# Sheet1.net
KiCad netlist of a schematic drawn in Altium Designer
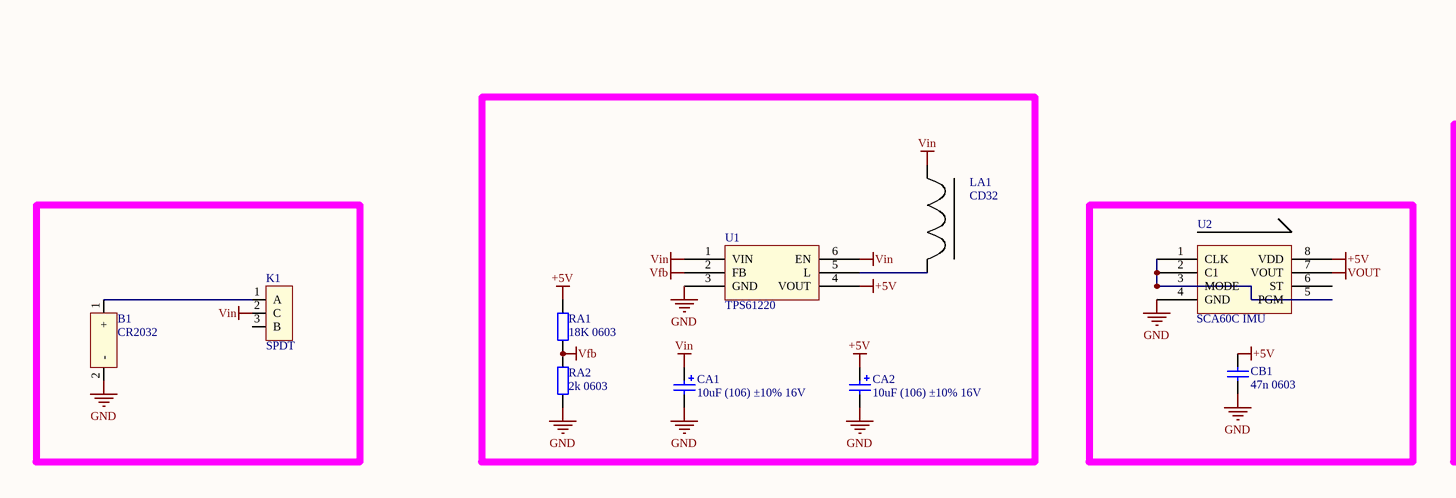
[diagram p0: Sheet1.SchDoc, left]
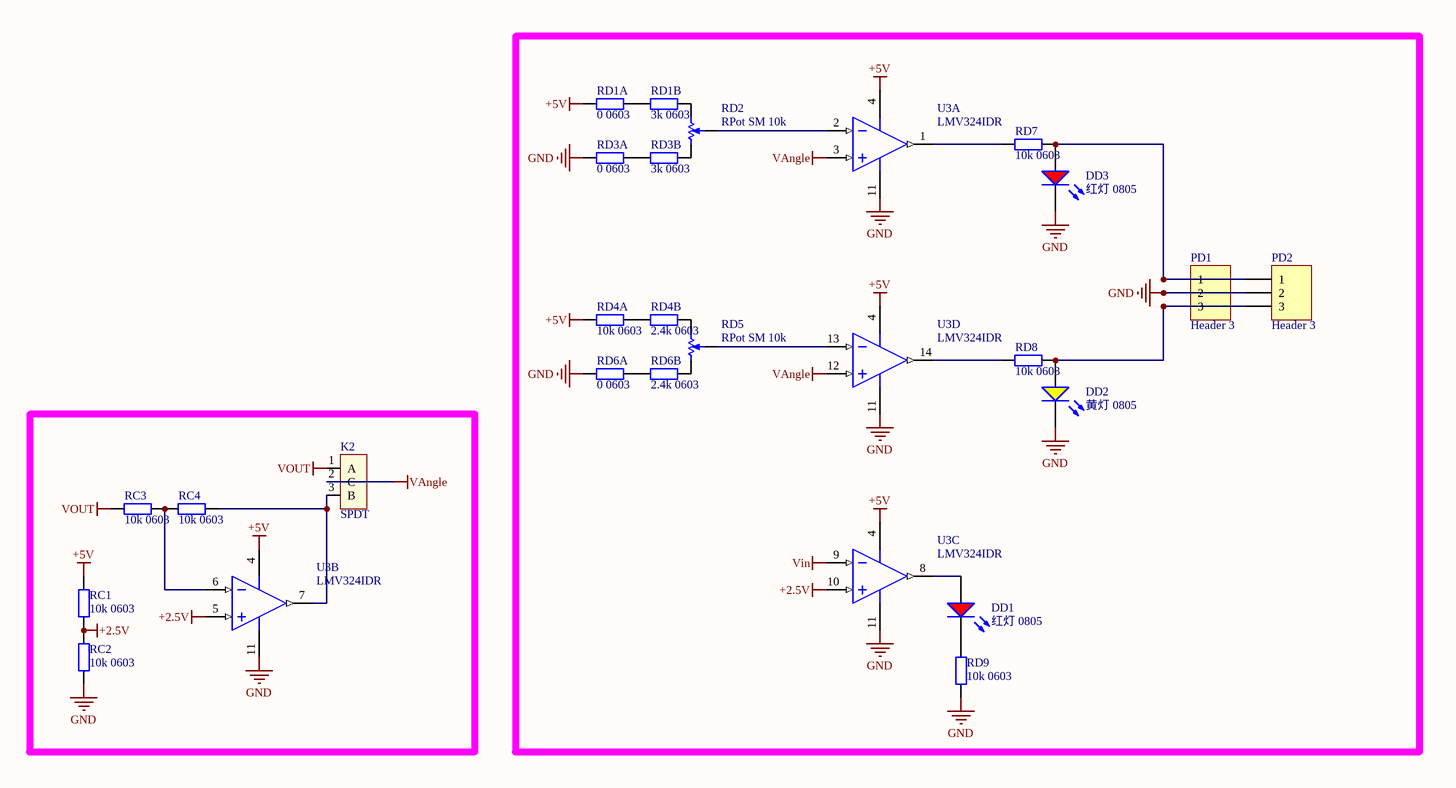
[diagram p1: Sheet1.SchDoc, right]

(export (version "E")
  (design (tool "Eeschema 10.0.6"))
  (components
    (comp (ref "B1")
      (value "CR2032")
      (footprint "CR2032")
      (description "Battery")
      (libsource (lib "EME_TX_Lib") (part "CR2032"))
    )
    (comp (ref "CA1")
      (value "10uF (106) ±10% 16V")
      (footprint "LC-CASE-A_3216")
      (description "钽电容")
      (libsource (lib "Miscellaneous Devices LC") (part "3216 10uF (106) 10% 16V"))
    )
    (comp (ref "CA2")
      (value "10uF (106) ±10% 16V")
      (footprint "LC-CASE-A_3216")
      (description "钽电容")
      (libsource (lib "Miscellaneous Devices LC") (part "3216 10uF (106) 10% 16V"))
    )
    (comp (ref "CB1")
      (value "47n 0603")
      (footprint "LC-0603_C")
      (description "贴片电容")
      (libsource (lib "Miscellaneous Devices LC") (part "0603 4.7nF (472) 10% 50V"))
    )
    (comp (ref "DD1")
      (value "红灯 0805")
      (footprint "LC-0805_LED_S1")
      (description "发光二极管")
      (libsource (lib "Miscellaneous Devices LC") (part "0805 红灯"))
    )
    (comp (ref "DD2")
      (value "黄灯 0805")
      (footprint "LC-0805_LED_S1")
      (description "发光二极管")
      (libsource (lib "Miscellaneous Devices LC") (part "0805 黄灯"))
    )
    (comp (ref "DD3")
      (value "红灯 0805")
      (footprint "LC-0805_LED_S1")
      (description "发光二极管")
      (libsource (lib "Miscellaneous Devices LC") (part "0805 红灯"))
    )
    (comp (ref "K1") (value "SPDT") (footprint "MSS22D18G2") (libsource (lib "EKAD") (part "MSS22D18G2")))
    (comp (ref "K2") (value "SPDT") (footprint "MSS22D18G2") (libsource (lib "EKAD") (part "MSS22D18G2")))
    (comp (ref "LA1") (value "CD32") (footprint "CD32") (libsource (lib "SMT_inductor") (part "CD32")))
    (comp (ref "PD1")
      (value "Header 3")
      (footprint "HDR1X3")
      (description "Header, 3-Pin")
      (fields (field (name "PUBLISHER") "Altium Limited"))
      (libsource (lib "Miscellaneous Connectors") (part "Header 3"))
    )
    (comp (ref "PD2")
      (value "Header 3")
      (footprint "HDR1X3")
      (description "Header, 3-Pin")
      (fields (field (name "PUBLISHER") "Altium Limited"))
      (libsource (lib "Miscellaneous Connectors") (part "Header 3"))
    )
    (comp (ref "RA1")
      (value "18K 0603")
      (footprint "LC-0603_R")
      (description "贴片电阻")
      (libsource (lib "Miscellaneous Devices LC") (part "0603 68Ω (68R0) 1%"))
    )
    (comp (ref "RA2")
      (value "2k 0603")
      (footprint "LC-0603_R")
      (description "贴片电阻")
      (libsource (lib "Miscellaneous Devices LC") (part "0603 68Ω (68R0) 1%"))
    )
    (comp (ref "RC1")
      (value "10k 0603")
      (footprint "LC-0603_R")
      (description "贴片电阻")
      (libsource (lib "Miscellaneous Devices LC") (part "0603 68Ω (68R0) 1%"))
    )
    (comp (ref "RC2")
      (value "10k 0603")
      (footprint "LC-0603_R")
      (description "贴片电阻")
      (libsource (lib "Miscellaneous Devices LC") (part "0603 68Ω (68R0) 1%"))
    )
    (comp (ref "RC3")
      (value "10k 0603")
      (footprint "LC-0603_R")
      (description "贴片电阻")
      (libsource (lib "") (part "0603 68Ω (68R0) 1%_1"))
    )
    (comp (ref "RC4")
      (value "10k 0603")
      (footprint "LC-0603_R")
      (description "贴片电阻")
      (libsource (lib "") (part "0603 68Ω (68R0) 1%_1"))
    )
    (comp (ref "RD1A")
      (value "0 0603")
      (footprint "LC-0603_R")
      (description "贴片电阻")
      (libsource (lib "") (part "0603 68Ω (68R0) 1%_1"))
    )
    (comp (ref "RD1B")
      (value "3k 0603")
      (footprint "LC-0603_R")
      (description "贴片电阻")
      (libsource (lib "") (part "0603 68Ω (68R0) 1%_1"))
    )
    (comp (ref "RD2")
      (value "RPot SM 10k")
      (footprint "POT4MM-2")
      (description "Square Trimming Potentiometer")
      (fields (field (name "PUBLISHER") "Altium Limited"))
      (libsource (lib "Miscellaneous Devices") (part "RPot SM"))
    )
    (comp (ref "RD3A")
      (value "0 0603")
      (footprint "LC-0603_R")
      (description "贴片电阻")
      (libsource (lib "") (part "0603 68Ω (68R0) 1%_1"))
    )
    (comp (ref "RD3B")
      (value "3k 0603")
      (footprint "LC-0603_R")
      (description "贴片电阻")
      (libsource (lib "") (part "0603 68Ω (68R0) 1%_1"))
    )
    (comp (ref "RD4A")
      (value "10k 0603")
      (footprint "LC-0603_R")
      (description "贴片电阻")
      (libsource (lib "") (part "0603 68Ω (68R0) 1%_1"))
    )
    (comp (ref "RD4B")
      (value "2.4k 0603")
      (footprint "LC-0603_R")
      (description "贴片电阻")
      (libsource (lib "") (part "0603 68Ω (68R0) 1%_1"))
    )
    (comp (ref "RD5")
      (value "RPot SM 10k")
      (footprint "POT4MM-2")
      (description "Square Trimming Potentiometer")
      (fields (field (name "PUBLISHER") "Altium Limited"))
      (libsource (lib "Miscellaneous Devices") (part "RPot SM"))
    )
    (comp (ref "RD6A")
      (value "0 0603")
      (footprint "LC-0603_R")
      (description "贴片电阻")
      (libsource (lib "") (part "0603 68Ω (68R0) 1%_1"))
    )
    (comp (ref "RD6B")
      (value "2.4k 0603")
      (footprint "LC-0603_R")
      (description "贴片电阻")
      (libsource (lib "") (part "0603 68Ω (68R0) 1%_1"))
    )
    (comp (ref "RD7")
      (value "10k 0603")
      (footprint "LC-0603_R")
      (description "贴片电阻")
      (libsource (lib "") (part "0603 68Ω (68R0) 1%_1"))
    )
    (comp (ref "RD8")
      (value "10k 0603")
      (footprint "LC-0603_R")
      (description "贴片电阻")
      (libsource (lib "") (part "0603 68Ω (68R0) 1%_2"))
    )
    (comp (ref "RD9")
      (value "10k 0603")
      (footprint "LC-0603_R")
      (description "贴片电阻")
      (libsource (lib "Miscellaneous Devices LC") (part "0603 68Ω (68R0) 1%"))
    )
    (comp (ref "U1")
      (value "TPS61220")
      (footprint "TPS61220")
      (description "Boost")
      (libsource (lib "EKAD") (part "TPS61220"))
    )
    (comp (ref "U2")
      (value "SCA60C IMU")
      (footprint "SCA60C")
      (description "Angle Sensor")
      (libsource (lib "EKAD") (part "SCA60C"))
    )
    (comp (ref "U3")
      (value "LMV324IDR")
      (footprint "LC-SOIC-14_150mil")
      (description "运放")
      (libsource (lib "Miscellaneous Devices LC") (part "LMV324IDR"))
    )
  )
  (nets
    (net (code "1") (name "+2.5V") (class "Default")
      (node (ref "RC1") (pin "1") (pinfunction "1_1") (pintype "passive"))
      (node (ref "RC2") (pin "2") (pinfunction "2_2") (pintype "passive"))
      (node (ref "U3") (pin "10") (pinfunction "INC+_10") (pintype "input"))
      (node (ref "U3") (pin "5") (pinfunction "INB+_5") (pintype "input"))
    )
    (net (code "2") (name "+5V") (class "Default")
      (node (ref "CA2") (pin "1") (pinfunction "1_1") (pintype "passive"))
      (node (ref "CB1") (pin "2") (pinfunction "2_2") (pintype "passive"))
      (node (ref "RA1") (pin "2") (pinfunction "2_2") (pintype "passive"))
      (node (ref "RC1") (pin "2") (pinfunction "2_2") (pintype "passive"))
      (node (ref "RD1A") (pin "2") (pinfunction "2_2") (pintype "passive"))
      (node (ref "RD4A") (pin "2") (pinfunction "2_2") (pintype "passive"))
      (node (ref "U1") (pin "4") (pinfunction "VOUT_4") (pintype "passive"))
      (node (ref "U2") (pin "8") (pinfunction "VDD_8") (pintype "passive"))
      (node (ref "U3") (pin "4") (pinfunction "V+_4") (pintype "power_in"))
    )
    (net (code "3") (name "GND") (class "Default")
      (node (ref "B1") (pin "2") (pinfunction "-_2") (pintype "passive"))
      (node (ref "CA1") (pin "2") (pinfunction "2_2") (pintype "passive"))
      (node (ref "CA2") (pin "2") (pinfunction "2_2") (pintype "passive"))
      (node (ref "CB1") (pin "1") (pinfunction "1_1") (pintype "passive"))
      (node (ref "DD2") (pin "K") (pinfunction "K_K") (pintype "passive"))
      (node (ref "DD3") (pin "K") (pinfunction "K_K") (pintype "passive"))
      (node (ref "PD1") (pin "2") (pinfunction "2_2") (pintype "passive"))
      (node (ref "PD2") (pin "2") (pinfunction "2_2") (pintype "passive"))
      (node (ref "RA2") (pin "1") (pinfunction "1_1") (pintype "passive"))
      (node (ref "RC2") (pin "1") (pinfunction "1_1") (pintype "passive"))
      (node (ref "RD3A") (pin "2") (pinfunction "2_2") (pintype "passive"))
      (node (ref "RD6A") (pin "2") (pinfunction "2_2") (pintype "passive"))
      (node (ref "RD9") (pin "1") (pinfunction "1_1") (pintype "passive"))
      (node (ref "U1") (pin "3") (pinfunction "GND_3") (pintype "passive"))
      (node (ref "U2") (pin "4") (pinfunction "GND_4") (pintype "passive"))
      (node (ref "U3") (pin "11") (pinfunction "V-_11") (pintype "power_in"))
    )
    (net (code "4") (name "Net-(B1-+)") (class "Default")
      (node (ref "B1") (pin "1") (pinfunction "+_1") (pintype "passive"))
      (node (ref "K1") (pin "1") (pinfunction "A_1") (pintype "passive"))
    )
    (net (code "5") (name "Net-(DD1-PadK)") (class "Default")
      (node (ref "DD1") (pin "K") (pinfunction "K_K") (pintype "passive"))
      (node (ref "RD9") (pin "2") (pinfunction "2_2") (pintype "passive"))
    )
    (net (code "6") (name "Net-(DD2-PadA)") (class "Default")
      (node (ref "DD2") (pin "A") (pinfunction "A_A") (pintype "passive"))
      (node (ref "PD1") (pin "3") (pinfunction "3_3") (pintype "passive"))
      (node (ref "PD2") (pin "3") (pinfunction "3_3") (pintype "passive"))
      (node (ref "RD8") (pin "2") (pinfunction "2_2") (pintype "passive"))
    )
    (net (code "7") (name "Net-(DD3-PadA)") (class "Default")
      (node (ref "DD3") (pin "A") (pinfunction "A_A") (pintype "passive"))
      (node (ref "PD1") (pin "1") (pinfunction "1_1") (pintype "passive"))
      (node (ref "PD2") (pin "1") (pinfunction "1_1") (pintype "passive"))
      (node (ref "RD7") (pin "1") (pinfunction "1_1") (pintype "passive"))
    )
    (net (code "8") (name "Net-(K2-B)") (class "Default")
      (node (ref "K2") (pin "3") (pinfunction "B_3") (pintype "passive"))
      (node (ref "RC4") (pin "1") (pinfunction "1_1") (pintype "passive"))
      (node (ref "U3") (pin "7") (pinfunction "OUTB_7") (pintype "output"))
    )
    (net (code "9") (name "Net-(RD1A-Pad1)") (class "Default")
      (node (ref "RD1A") (pin "1") (pinfunction "1_1") (pintype "passive"))
      (node (ref "RD1B") (pin "2") (pinfunction "2_2") (pintype "passive"))
    )
    (net (code "10") (name "Net-(RD2-+)") (class "Default")
      (node (ref "RD1B") (pin "1") (pinfunction "1_1") (pintype "passive"))
      (node (ref "RD2") (pin "CW") (pinfunction "+_CW") (pintype "passive"))
    )
    (net (code "11") (name "Net-(RD2--)") (class "Default")
      (node (ref "RD2") (pin "CCW") (pinfunction "-_CCW") (pintype "passive"))
      (node (ref "RD3B") (pin "1") (pinfunction "1_1") (pintype "passive"))
    )
    (net (code "12") (name "Net-(RD3A-Pad1)") (class "Default")
      (node (ref "RD3A") (pin "1") (pinfunction "1_1") (pintype "passive"))
      (node (ref "RD3B") (pin "2") (pinfunction "2_2") (pintype "passive"))
    )
    (net (code "13") (name "Net-(RD4A-Pad1)") (class "Default")
      (node (ref "RD4A") (pin "1") (pinfunction "1_1") (pintype "passive"))
      (node (ref "RD4B") (pin "2") (pinfunction "2_2") (pintype "passive"))
    )
    (net (code "14") (name "Net-(RD5-+)") (class "Default")
      (node (ref "RD4B") (pin "1") (pinfunction "1_1") (pintype "passive"))
      (node (ref "RD5") (pin "CW") (pinfunction "+_CW") (pintype "passive"))
    )
    (net (code "15") (name "Net-(RD5--)") (class "Default")
      (node (ref "RD5") (pin "CCW") (pinfunction "-_CCW") (pintype "passive"))
      (node (ref "RD6B") (pin "1") (pinfunction "1_1") (pintype "passive"))
    )
    (net (code "16") (name "Net-(RD6A-Pad1)") (class "Default")
      (node (ref "RD6A") (pin "1") (pinfunction "1_1") (pintype "passive"))
      (node (ref "RD6B") (pin "2") (pinfunction "2_2") (pintype "passive"))
    )
    (net (code "17") (name "Net-(U1-L)") (class "Default")
      (node (ref "LA1") (pin "2") (pinfunction "2_2") (pintype "passive"))
      (node (ref "U1") (pin "5") (pinfunction "L_5") (pintype "passive"))
    )
    (net (code "18") (name "Net-(U2-C1)") (class "Default")
      (node (ref "U2") (pin "1") (pinfunction "CLK_1") (pintype "passive"))
      (node (ref "U2") (pin "2") (pinfunction "C1_2") (pintype "passive"))
      (node (ref "U2") (pin "3") (pinfunction "MODE_3") (pintype "passive"))
      (node (ref "U2") (pin "5") (pinfunction "PGM_5") (pintype "passive"))
    )
    (net (code "19") (name "Net-(U3A-INA-)") (class "Default")
      (node (ref "RD2") (pin "W") (pinfunction "W_W") (pintype "passive"))
      (node (ref "U3") (pin "2") (pinfunction "INA-_2") (pintype "input"))
    )
    (net (code "20") (name "Net-(U3A-OUTA)") (class "Default")
      (node (ref "RD7") (pin "2") (pinfunction "2_2") (pintype "passive"))
      (node (ref "U3") (pin "1") (pinfunction "OUTA_1") (pintype "output"))
    )
    (net (code "21") (name "Net-(U3B-INB-)") (class "Default")
      (node (ref "RC3") (pin "1") (pinfunction "1_1") (pintype "passive"))
      (node (ref "RC4") (pin "2") (pinfunction "2_2") (pintype "passive"))
      (node (ref "U3") (pin "6") (pinfunction "INB-_6") (pintype "input"))
    )
    (net (code "22") (name "Net-(U3C-OUTC)") (class "Default")
      (node (ref "DD1") (pin "A") (pinfunction "A_A") (pintype "passive"))
      (node (ref "U3") (pin "8") (pinfunction "OUTC_8") (pintype "output"))
    )
    (net (code "23") (name "Net-(U3D-IND-)") (class "Default")
      (node (ref "RD5") (pin "W") (pinfunction "W_W") (pintype "passive"))
      (node (ref "U3") (pin "13") (pinfunction "IND-_13") (pintype "input"))
    )
    (net (code "24") (name "Net-(U3D-OUTD)") (class "Default")
      (node (ref "RD8") (pin "1") (pinfunction "1_1") (pintype "passive"))
      (node (ref "U3") (pin "14") (pinfunction "OUTD_14") (pintype "output"))
    )
    (net (code "25") (name "VAngle") (class "Default")
      (node (ref "K2") (pin "2") (pinfunction "C_2") (pintype "passive"))
      (node (ref "U3") (pin "12") (pinfunction "IND+_12") (pintype "input"))
      (node (ref "U3") (pin "3") (pinfunction "INA+_3") (pintype "input"))
    )
    (net (code "26") (name "VOUT") (class "Default")
      (node (ref "K2") (pin "1") (pinfunction "A_1") (pintype "passive"))
      (node (ref "RC3") (pin "2") (pinfunction "2_2") (pintype "passive"))
      (node (ref "U2") (pin "7") (pinfunction "VOUT_7") (pintype "passive"))
    )
    (net (code "27") (name "Vfb") (class "Default")
      (node (ref "RA1") (pin "1") (pinfunction "1_1") (pintype "passive"))
      (node (ref "RA2") (pin "2") (pinfunction "2_2") (pintype "passive"))
      (node (ref "U1") (pin "2") (pinfunction "FB_2") (pintype "passive"))
    )
    (net (code "28") (name "Vin") (class "Default")
      (node (ref "CA1") (pin "1") (pinfunction "1_1") (pintype "passive"))
      (node (ref "K1") (pin "2") (pinfunction "C_2") (pintype "passive"))
      (node (ref "LA1") (pin "1") (pinfunction "1_1") (pintype "passive"))
      (node (ref "U1") (pin "1") (pinfunction "VIN_1") (pintype "passive"))
      (node (ref "U1") (pin "6") (pinfunction "EN_6") (pintype "passive"))
      (node (ref "U3") (pin "9") (pinfunction "INC-_9") (pintype "input"))
    )
    (net (code "29") (name "unconnected-(K1-B-Pad3)") (class "Default")
      (node (ref "K1") (pin "3") (pinfunction "B_3") (pintype "passive"))
    )
    (net (code "30") (name "unconnected-(U2-ST-Pad6)") (class "Default")
      (node (ref "U2") (pin "6") (pinfunction "ST_6") (pintype "passive"))
    )
  )
)
